# DetectorLogic.net
KiCad netlist of a schematic drawn in Altium Designer
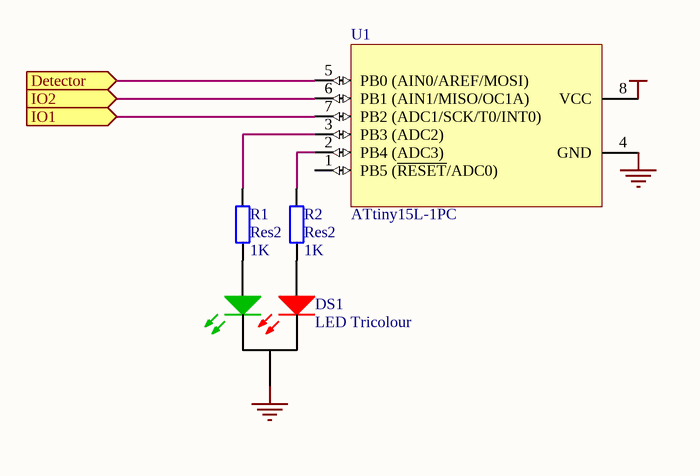
[diagram p0: DetectorLogic.SchDoc]

(export (version "E")
  (design (tool "Eeschema 10.0.6"))
  (components
    (comp (ref "DS1")
      (value "LED Tricolour")
      (footprint "LED5mm TriColour")
      (description "Typical Red Green Tri Color LED")
      (fields (field (name "PUBLISHER") "Altium Limited"))
      (libsource (lib "Custom") (part "LED Tricolour"))
    )
    (comp (ref "R1")
      (value "Res2")
      (footprint "AXIAL-0.4")
      (description "Resistor")
      (fields (field (name "ALTIUM_VALUE") "1K") (field (name "PUBLISHER") "Altium Limited"))
      (libsource (lib "Miscellaneous Devices") (part "Res2"))
    )
    (comp (ref "R2")
      (value "Res2")
      (footprint "AXIAL-0.4")
      (description "Resistor")
      (fields (field (name "ALTIUM_VALUE") "1K") (field (name "PUBLISHER") "Altium Limited"))
      (libsource (lib "Miscellaneous Devices") (part "Res2"))
    )
    (comp (ref "U1")
      (value "ATtiny15L-1PC")
      (footprint "8P3")
      (description "8-Bit AVR Microcontroller with 1K Byte of Flash Memory")
      (fields (field (name "PUBLISHER") "Altium Limited"))
      (libsource (lib "Atmel Microcontroller 8-Bit AVR") (part "ATtiny15L-1PC"))
    )
  )
  (nets
    (net (code "1") (name "/Detector") (class "Default")
      (node (ref "U1") (pin "5") (pinfunction "PB0_(AIN0/AREF/MOSI)_5") (pintype "bidirectional"))
    )
    (net (code "2") (name "/IO1") (class "Default")
      (node (ref "U1") (pin "7") (pinfunction "PB2_(ADC1/SCK/T0/INT0)_7") (pintype "bidirectional"))
    )
    (net (code "3") (name "/IO2") (class "Default")
      (node (ref "U1") (pin "6") (pinfunction "PB1_(AIN1/MISO/OC1A)_6") (pintype "bidirectional"))
    )
    (net (code "4") (name "GND") (class "Default")
      (node (ref "DS1") (pin "2") (pinfunction "K_2") (pintype "passive"))
      (node (ref "U1") (pin "4") (pinfunction "GND_4") (pintype "power_in"))
    )
    (net (code "5") (name "Net-(DS1-Ag)") (class "Default")
      (node (ref "DS1") (pin "1") (pinfunction "Ag_1") (pintype "passive"))
      (node (ref "R1") (pin "2") (pinfunction "2_2") (pintype "passive"))
    )
    (net (code "6") (name "Net-(DS1-Ar)") (class "Default")
      (node (ref "DS1") (pin "3") (pinfunction "Ar_3") (pintype "passive"))
      (node (ref "R2") (pin "2") (pinfunction "2_2") (pintype "passive"))
    )
    (net (code "7") (name "Net-(U1-PB3_(ADC2))") (class "Default")
      (node (ref "R1") (pin "1") (pinfunction "1_1") (pintype "passive"))
      (node (ref "U1") (pin "3") (pinfunction "PB3_(ADC2)_3") (pintype "bidirectional"))
    )
    (net (code "8") (name "Net-(U1-PB4_(ADC3))") (class "Default")
      (node (ref "R2") (pin "1") (pinfunction "1_1") (pintype "passive"))
      (node (ref "U1") (pin "2") (pinfunction "PB4_(ADC3)_2") (pintype "bidirectional"))
    )
    (net (code "9") (name "VCC") (class "Default")
      (node (ref "U1") (pin "8") (pinfunction "VCC_8") (pintype "power_in"))
    )
    (net (code "10") (name "unconnected-(U1-PB5_(~{RESET}{slash}ADC0)-Pad1)") (class "Default")
      (node (ref "U1") (pin "1") (pinfunction "PB5_(~{RESET}/ADC0)_1") (pintype "bidirectional"))
    )
  )
)
